# SEP00949BG.net
KiCad netlist of a schematic drawn in Altium Designer
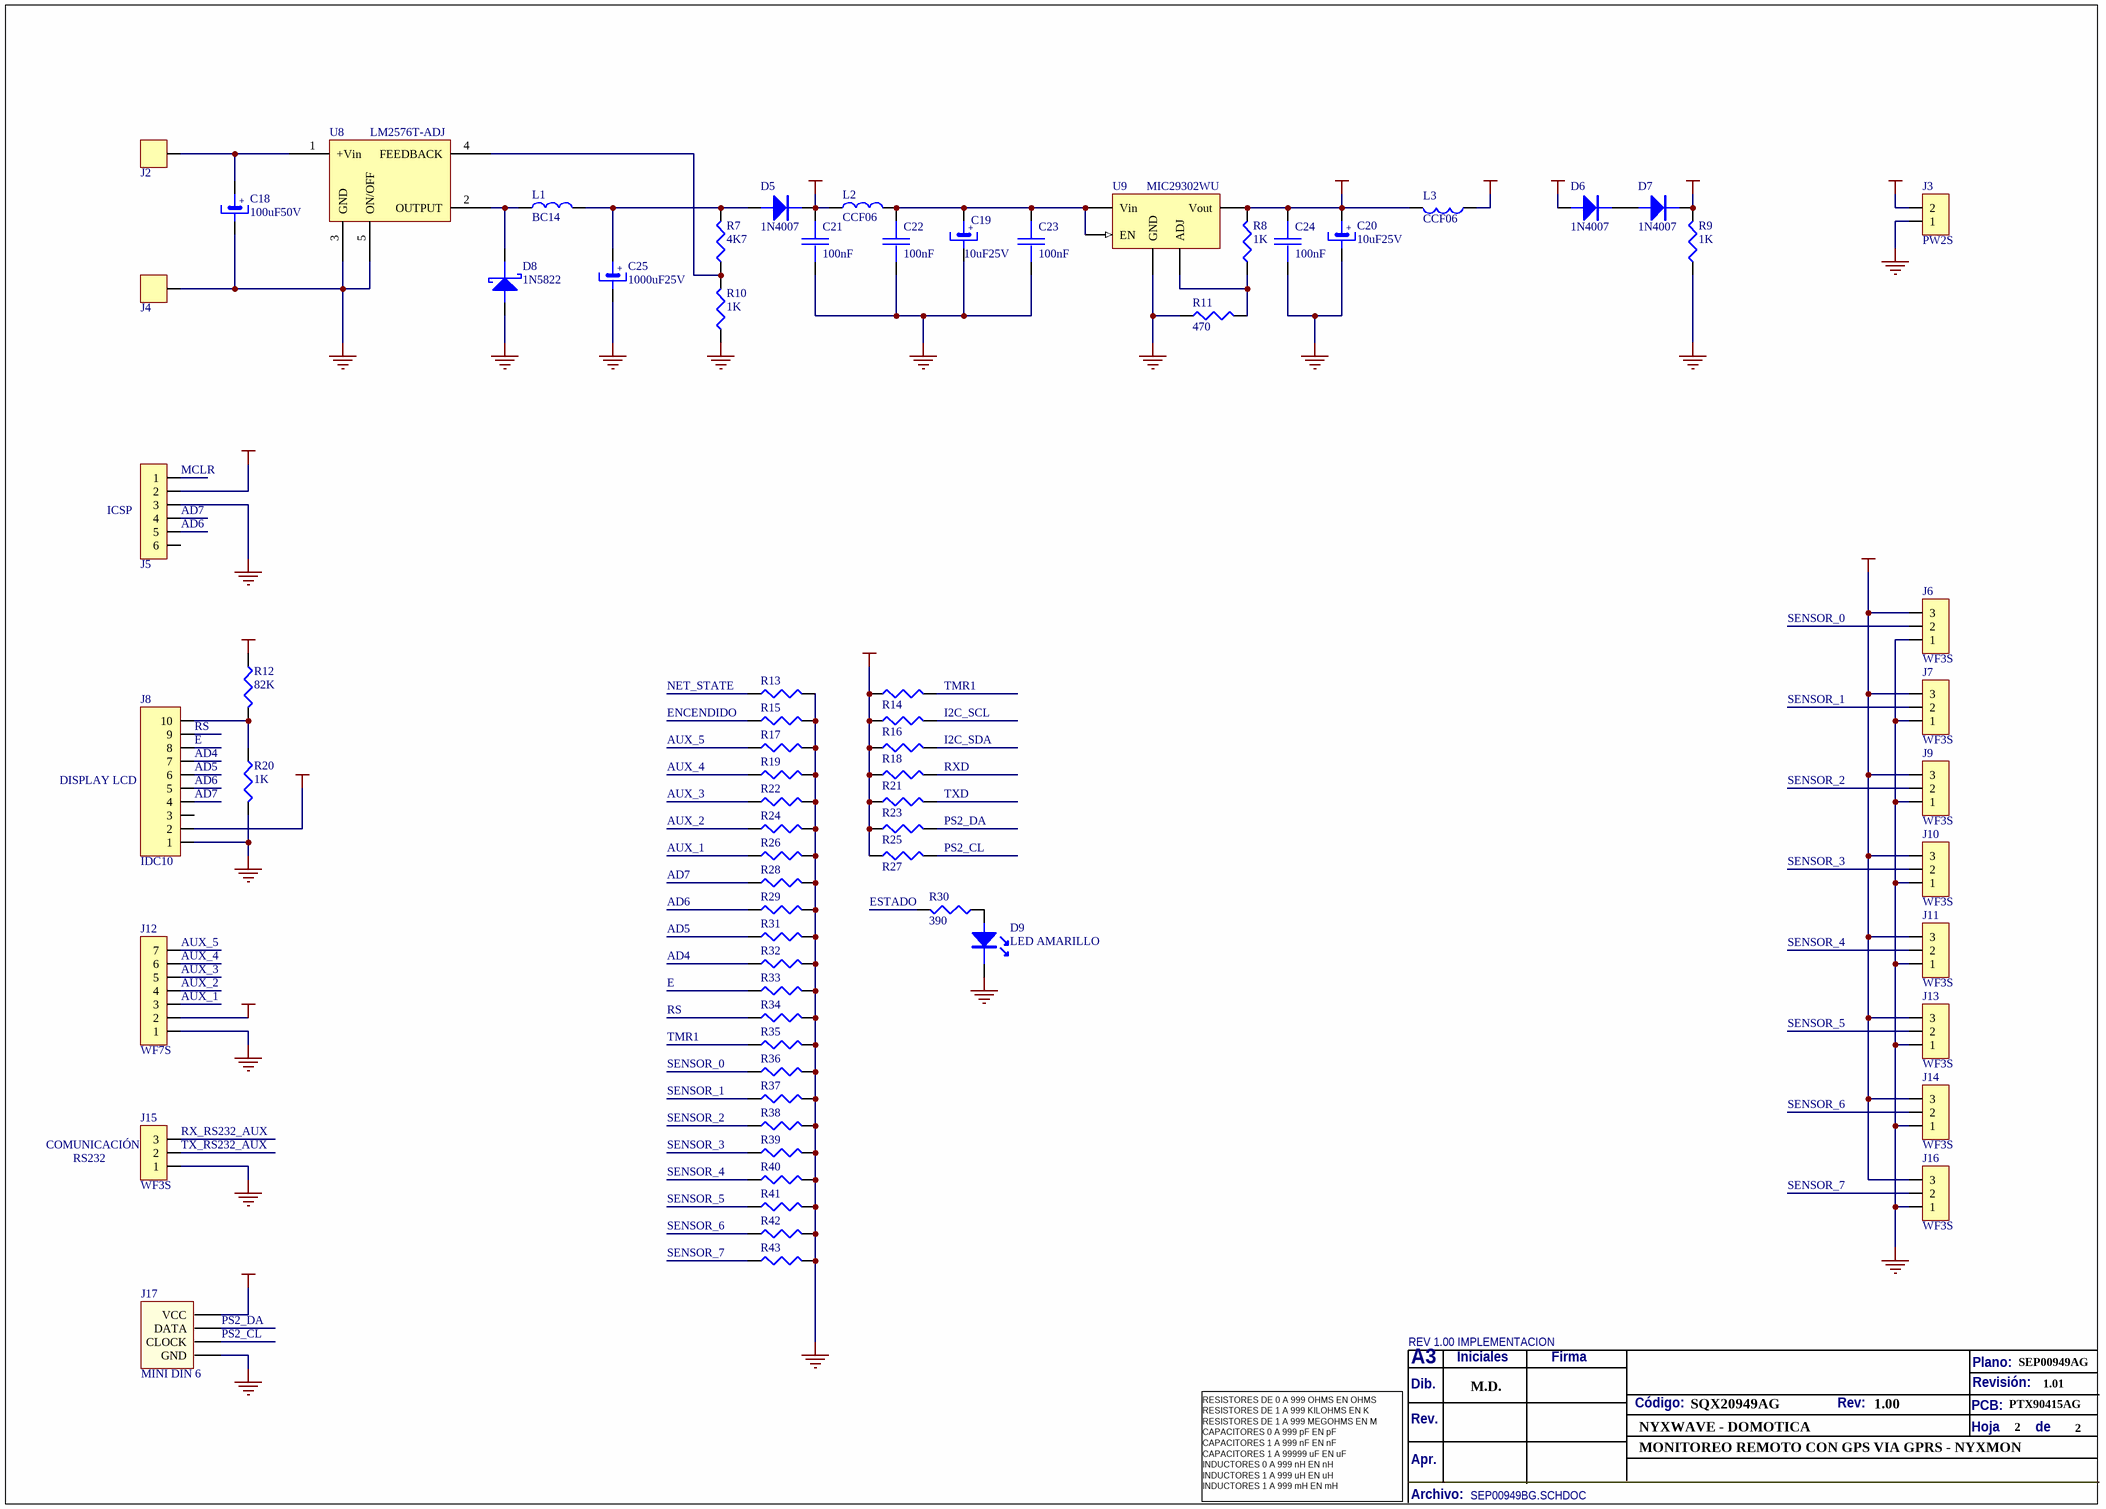
[diagram p0: SEP00949BG.SCHDOC]

(export (version "E")
  (design (tool "Eeschema 10.0.6"))
  (components
    (comp (ref "C18")
      (value "100uF50V")
      (footprint "CE 5.0/10.0")
      (description "CAPACITOR ELECTROLITICO RADIAL 10 X12 mm PASO 5 mm 50 V 100 uF")
      (libsource (lib "CAPACITORES ELECTROLITICOS") (part "100uF50V"))
    )
    (comp (ref "C19")
      (value "10uF25V")
      (footprint "CE 1.5/4.0")
      (description "CAPACITOR ELECTROLITICO RADIAL 5X7mm PASO 1.5mm 85ªC +/-20 25V 10uF")
      (libsource (lib "CAPACITORES ELECTROLITICOS") (part "10uF25V 4X7X1.5"))
    )
    (comp (ref "C20")
      (value "10uF25V")
      (footprint "CE 1.5/4.0")
      (description "CAPACITOR ELECTROLITICO RADIAL 5X7mm PASO 1.5mm 85ªC +/-20 25V 10uF")
      (libsource (lib "CAPACITORES ELECTROLITICOS") (part "10uF25V 4X7X1.5"))
    )
    (comp (ref "C21")
      (value "100nF")
      (footprint "0805")
      (description "CAPACITOR SMD 0805 X7R  50 V 100 nF")
      (libsource (lib "CAPACITORES SMD0805") (part "100n"))
    )
    (comp (ref "C22")
      (value "100nF")
      (footprint "0805")
      (description "CAPACITOR SMD 0805 X7R  50 V 100 nF")
      (libsource (lib "CAPACITORES SMD0805") (part "100n"))
    )
    (comp (ref "C23")
      (value "100nF")
      (footprint "0805")
      (description "CAPACITOR SMD 0805 X7R  50 V 100 nF")
      (libsource (lib "CAPACITORES SMD0805") (part "100n"))
    )
    (comp (ref "C24")
      (value "100nF")
      (footprint "0805")
      (description "CAPACITOR SMD 0805 X7R  50 V 100 nF")
      (libsource (lib "CAPACITORES SMD0805") (part "100n"))
    )
    (comp (ref "C25")
      (value "1000uF25V")
      (footprint "CE 5.0/10.0")
      (description "CAP ELECT RAD 1000UF 25V 10X20MM PASO 5MM 85ºC 20%")
      (libsource (lib "CAPACITORES ELECTROLITICOS") (part "1000uF25V"))
    )
    (comp (ref "D5")
      (value "1N4007")
      (footprint "DO-41_300")
      (description "1N4007 DO-41 DIODO")
      (libsource (lib "DIODOS") (part "1N4007 DO-41"))
    )
    (comp (ref "D6")
      (value "1N4007")
      (footprint "DO-41_300")
      (description "1N4007 DO-41 DIODO")
      (libsource (lib "DIODOS") (part "1N4007 DO-41"))
    )
    (comp (ref "D7")
      (value "1N4007")
      (footprint "DO-41_300")
      (description "1N4007 DO-41 DIODO")
      (libsource (lib "DIODOS") (part "1N4007 DO-41"))
    )
    (comp (ref "D8")
      (value "1N5822")
      (footprint "DO-201_300")
      (description "1N5822 DO-201 DIODO")
      (libsource (lib "DIODOS") (part "1N5822 DO-201"))
    )
    (comp (ref "D9")
      (value "LED AMARILLO")
      (footprint "LED 3MM")
      (description "LED AMARILLO 3MM")
      (libsource (lib "DIODOS") (part "LED AMARILLO 3MM"))
    )
    (comp (ref "J2")
      (value "WAGO236")
      (footprint "wago236")
      (description "WAGO 236-401 BORNE GRIS CLARO")
      (libsource (lib "CONECTORES") (part "WAGO 236"))
    )
    (comp (ref "J3")
      (value "PW2S")
      (footprint "PW2S")
      (description "PW2S HEADER .156\" RECTO 2 VIAS")
      (libsource (lib "CONECTORES") (part "PW2S"))
    )
    (comp (ref "J4")
      (value "WAGO236")
      (footprint "wago236")
      (description "WAGO 236-401 BORNE GRIS CLARO")
      (libsource (lib "CONECTORES") (part "WAGO 236"))
    )
    (comp (ref "J5")
      (value "HEADER6")
      (footprint "JUMPER_6A")
      (description "TIRA MOLEX 1X6 11MM MACHO RECTA PARA PCB")
      (libsource (lib "CONECTORES") (part "HEADER6"))
    )
    (comp (ref "J6")
      (value "WF3S")
      (footprint "WF3S")
      (description "WF3S HEADER .100\" RECTO 3 VIAS")
      (libsource (lib "CONECTORES") (part "WF3S"))
    )
    (comp (ref "J7")
      (value "WF3S")
      (footprint "WF3S")
      (description "WF3S HEADER .100\" RECTO 3 VIAS")
      (libsource (lib "CONECTORES") (part "WF3S"))
    )
    (comp (ref "J8")
      (value "IDC10")
      (footprint "IDC10")
      (description "CONECTOR IDC HEMBRA PCB NO POLARIZADO PASO 2.54 mm RECTO 2X5 VIAS")
      (libsource (lib "CONECTORES") (part "IDC10"))
    )
    (comp (ref "J9")
      (value "WF3S")
      (footprint "WF3S")
      (description "WF3S HEADER .100\" RECTO 3 VIAS")
      (libsource (lib "CONECTORES") (part "WF3S"))
    )
    (comp (ref "J10")
      (value "WF3S")
      (footprint "WF3S")
      (description "WF3S HEADER .100\" RECTO 3 VIAS")
      (libsource (lib "CONECTORES") (part "WF3S"))
    )
    (comp (ref "J11")
      (value "WF3S")
      (footprint "WF3S")
      (description "WF3S HEADER .100\" RECTO 3 VIAS")
      (libsource (lib "CONECTORES") (part "WF3S"))
    )
    (comp (ref "J12")
      (value "WF7S")
      (footprint "WF7S")
      (description "WF7S HEADER .100\" RECTO 7 VIAS")
      (libsource (lib "CONECTORES") (part "WF7S"))
    )
    (comp (ref "J13")
      (value "WF3S")
      (footprint "WF3S")
      (description "WF3S HEADER .100\" RECTO 3 VIAS")
      (libsource (lib "CONECTORES") (part "WF3S"))
    )
    (comp (ref "J14")
      (value "WF3S")
      (footprint "WF3S")
      (description "WF3S HEADER .100\" RECTO 3 VIAS")
      (libsource (lib "CONECTORES") (part "WF3S"))
    )
    (comp (ref "J15")
      (value "WF3S")
      (footprint "WF3S")
      (description "WF3S HEADER .100\" RECTO 3 VIAS")
      (libsource (lib "") (part "WF3S_1"))
    )
    (comp (ref "J16")
      (value "WF3S")
      (footprint "WF3S")
      (description "WF3S HEADER .100\" RECTO 3 VIAS")
      (libsource (lib "CONECTORES") (part "WF3S"))
    )
    (comp (ref "J17")
      (value "MINI DIN 6")
      (footprint "MINI DIN PCB")
      (description "CONECTOR MINI DIN 6 PARA PCB")
      (libsource (lib "mini din") (part "CONECTOR MINI DIN 6"))
    )
    (comp (ref "L1")
      (value "BC14")
      (footprint "BCC")
      (description "INDUCTOR BC14")
      (libsource (lib "INDUCTORES") (part "BC14"))
    )
    (comp (ref "L2")
      (value "CCF06")
      (footprint "AXIAL10X4_300")
      (description "INDUCTOR CCF06")
      (libsource (lib "INDUCTORES") (part "CCF06"))
    )
    (comp (ref "L3")
      (value "CCF06")
      (footprint "AXIAL10X4_300")
      (description "INDUCTOR CCF06")
      (libsource (lib "INDUCTORES") (part "CCF06"))
    )
    (comp (ref "R7")
      (value "4K7")
      (footprint "RES_MF1/2W_200")
      (description "RESISTOR METAL FILM 0.5 W 5% 4.7 KILOHMS")
      (libsource (lib "RESISTORES METAL FILM MEDIO WATT") (part "4K7"))
    )
    (comp (ref "R8")
      (value "1K")
      (footprint "RES_MF1/2W_200")
      (description "RESISTOR METAL FILM 0.5 W 5% 1 K OHMS")
      (libsource (lib "RESISTORES METAL FILM MEDIO WATT") (part "1K"))
    )
    (comp (ref "R9")
      (value "1K")
      (footprint "RES_MF1/2W_200")
      (description "RESISTOR METAL FILM 0.5 W 5% 1 K OHMS")
      (libsource (lib "RESISTORES METAL FILM MEDIO WATT") (part "1K"))
    )
    (comp (ref "R10")
      (value "1K")
      (footprint "RES_MF1/2W_200")
      (description "RESISTOR METAL FILM 0.5 W 5% 1 K OHMS")
      (libsource (lib "RESISTORES METAL FILM MEDIO WATT") (part "1K"))
    )
    (comp (ref "R11")
      (value "470")
      (footprint "RES_MF1/2W_200")
      (description "RESISTOR METAL FILM 0.5 W 5% 470 OHMS")
      (libsource (lib "RESISTORES METAL FILM MEDIO WATT") (part "470"))
    )
    (comp (ref "R12")
      (value "82K")
      (footprint "RES_MF1/2W_200")
      (description "RESISTOR METAL FILM 0.5 W 5% 82 KILOHMS")
      (libsource (lib "RESISTORES METAL FILM MEDIO WATT") (part "82K"))
    )
    (comp (ref "R13")
      (value "5K6")
      (footprint "0805")
      (description "RESISTOR SMD0805 0.125 W 5%  5.6 K OHMS")
      (libsource (lib "RESISTORES SMD0805") (part "5K6"))
    )
    (comp (ref "R14")
      (value "5K6")
      (footprint "0805")
      (description "RESISTOR SMD0805 0.125 W 5%  5.6 K OHMS")
      (libsource (lib "RESISTORES SMD0805") (part "5K6"))
    )
    (comp (ref "R15")
      (value "5K6")
      (footprint "0805")
      (description "RESISTOR SMD0805 0.125 W 5%  5.6 K OHMS")
      (libsource (lib "RESISTORES SMD0805") (part "5K6"))
    )
    (comp (ref "R16")
      (value "10K")
      (footprint "0805")
      (description "RESISTOR SMD0805 0.125 W 5%  10 K OHMS")
      (libsource (lib "RESISTORES SMD0805") (part "10K"))
    )
    (comp (ref "R17")
      (value "5K6")
      (footprint "0805")
      (description "RESISTOR SMD0805 0.125 W 5%  5.6 K OHMS")
      (libsource (lib "RESISTORES SMD0805") (part "5K6"))
    )
    (comp (ref "R18")
      (value "10K")
      (footprint "0805")
      (description "RESISTOR SMD0805 0.125 W 5%  10 K OHMS")
      (libsource (lib "RESISTORES SMD0805") (part "10K"))
    )
    (comp (ref "R19")
      (value "5K6")
      (footprint "0805")
      (description "RESISTOR SMD0805 0.125 W 5%  5.6 K OHMS")
      (libsource (lib "RESISTORES SMD0805") (part "5K6"))
    )
    (comp (ref "R20")
      (value "1K")
      (footprint "RES_MF1/2W_200")
      (description "RESISTOR METAL FILM 0.5 W 5% 1 K OHMS")
      (libsource (lib "RESISTORES METAL FILM MEDIO WATT") (part "1K"))
    )
    (comp (ref "R21")
      (value "100K")
      (footprint "0805")
      (description "RESISTOR SMD0805 0.125 W 5%  100 K OHMS")
      (libsource (lib "RESISTORES SMD0805") (part "100K"))
    )
    (comp (ref "R22")
      (value "5K6")
      (footprint "0805")
      (description "RESISTOR SMD0805 0.125 W 5%  5.6 K OHMS")
      (libsource (lib "RESISTORES SMD0805") (part "5K6"))
    )
    (comp (ref "R23")
      (value "100K")
      (footprint "0805")
      (description "RESISTOR SMD0805 0.125 W 5%  100 K OHMS")
      (libsource (lib "RESISTORES SMD0805") (part "100K"))
    )
    (comp (ref "R24")
      (value "5K6")
      (footprint "0805")
      (description "RESISTOR SMD0805 0.125 W 5%  5.6 K OHMS")
      (libsource (lib "RESISTORES SMD0805") (part "5K6"))
    )
    (comp (ref "R25")
      (value "5K6")
      (footprint "0805")
      (description "RESISTOR SMD0805 0.125 W 5%  5.6 K OHMS")
      (libsource (lib "RESISTORES SMD0805") (part "5K6"))
    )
    (comp (ref "R26")
      (value "5K6")
      (footprint "0805")
      (description "RESISTOR SMD0805 0.125 W 5%  5.6 K OHMS")
      (libsource (lib "RESISTORES SMD0805") (part "5K6"))
    )
    (comp (ref "R27")
      (value "5K6")
      (footprint "0805")
      (description "RESISTOR SMD0805 0.125 W 5%  5.6 K OHMS")
      (libsource (lib "RESISTORES SMD0805") (part "5K6"))
    )
    (comp (ref "R28")
      (value "5K6")
      (footprint "0805")
      (description "RESISTOR SMD0805 0.125 W 5%  5.6 K OHMS")
      (libsource (lib "RESISTORES SMD0805") (part "5K6"))
    )
    (comp (ref "R29")
      (value "5K6")
      (footprint "0805")
      (description "RESISTOR SMD0805 0.125 W 5%  5.6 K OHMS")
      (libsource (lib "RESISTORES SMD0805") (part "5K6"))
    )
    (comp (ref "R30")
      (value "390")
      (footprint "RES_MF1/2W_200")
      (description "RESISTOR METAL FILM 0.5 W 5% 390 OHMS")
      (libsource (lib "RESISTORES METAL FILM MEDIO WATT") (part "390"))
    )
    (comp (ref "R31")
      (value "5K6")
      (footprint "0805")
      (description "RESISTOR SMD0805 0.125 W 5%  5.6 K OHMS")
      (libsource (lib "RESISTORES SMD0805") (part "5K6"))
    )
    (comp (ref "R32")
      (value "5K6")
      (footprint "0805")
      (description "RESISTOR SMD0805 0.125 W 5%  5.6 K OHMS")
      (libsource (lib "RESISTORES SMD0805") (part "5K6"))
    )
    (comp (ref "R33")
      (value "5K6")
      (footprint "0805")
      (description "RESISTOR SMD0805 0.125 W 5%  5.6 K OHMS")
      (libsource (lib "RESISTORES SMD0805") (part "5K6"))
    )
    (comp (ref "R34")
      (value "5K6")
      (footprint "0805")
      (description "RESISTOR SMD0805 0.125 W 5%  5.6 K OHMS")
      (libsource (lib "RESISTORES SMD0805") (part "5K6"))
    )
    (comp (ref "R35")
      (value "5K6")
      (footprint "0805")
      (description "RESISTOR SMD0805 0.125 W 5%  5.6 K OHMS")
      (libsource (lib "RESISTORES SMD0805") (part "5K6"))
    )
    (comp (ref "R36")
      (value "150K")
      (footprint "0805")
      (description "RESISTOR SMD0805 0.125 W 5%  150 K OHMS")
      (libsource (lib "RESISTORES SMD0805") (part "150K"))
    )
    (comp (ref "R37")
      (value "150K")
      (footprint "0805")
      (description "RESISTOR SMD0805 0.125 W 5%  150 K OHMS")
      (libsource (lib "RESISTORES SMD0805") (part "150K"))
    )
    (comp (ref "R38")
      (value "150K")
      (footprint "0805")
      (description "RESISTOR SMD0805 0.125 W 5%  150 K OHMS")
      (libsource (lib "RESISTORES SMD0805") (part "150K"))
    )
    (comp (ref "R39")
      (value "150K")
      (footprint "0805")
      (description "RESISTOR SMD0805 0.125 W 5%  150 K OHMS")
      (libsource (lib "RESISTORES SMD0805") (part "150K"))
    )
    (comp (ref "R40")
      (value "150K")
      (footprint "0805")
      (description "RESISTOR SMD0805 0.125 W 5%  150 K OHMS")
      (libsource (lib "RESISTORES SMD0805") (part "150K"))
    )
    (comp (ref "R41")
      (value "150K")
      (footprint "0805")
      (description "RESISTOR SMD0805 0.125 W 5%  150 K OHMS")
      (libsource (lib "RESISTORES SMD0805") (part "150K"))
    )
    (comp (ref "R42")
      (value "150K")
      (footprint "0805")
      (description "RESISTOR SMD0805 0.125 W 5%  150 K OHMS")
      (libsource (lib "RESISTORES SMD0805") (part "150K"))
    )
    (comp (ref "R43")
      (value "150K")
      (footprint "0805")
      (description "RESISTOR SMD0805 0.125 W 5%  150 K OHMS")
      (libsource (lib "RESISTORES SMD0805") (part "150K"))
    )
    (comp (ref "U8")
      (value "LM2576T-ADJ")
      (footprint "TO-220-5V")
      (description "LM2576T-ADJ TO-220-5 CIRC INT")
      (libsource (lib "CIRCUITOS INTEGRADOS DIP") (part "LM2576T-ADJ"))
    )
    (comp (ref "U9")
      (value "MIC29302WU")
      (footprint "TO-220-5S")
      (description "MIC29302WU TO-220 (T) HIGH CURRENT LOW DROPOUT REGULATORS")
      (libsource (lib "CIRCUITOS INTEGRADOS DIP") (part "MIC29302WU"))
    )
  )
  (nets
    (net (code "1") (name "+5V") (class "Default")
      (node (ref "C20") (pin "1") (pinfunction "1_1") (pintype "passive"))
      (node (ref "C24") (pin "2") (pintype "passive"))
      (node (ref "D6") (pin "A") (pinfunction "A_A") (pintype "passive"))
      (node (ref "J10") (pin "3") (pinfunction "3_3") (pintype "passive"))
      (node (ref "J11") (pin "3") (pinfunction "3_3") (pintype "passive"))
      (node (ref "J12") (pin "2") (pinfunction "2_2") (pintype "passive"))
      (node (ref "J13") (pin "3") (pinfunction "3_3") (pintype "passive"))
      (node (ref "J14") (pin "3") (pinfunction "3_3") (pintype "passive"))
      (node (ref "J16") (pin "3") (pinfunction "3_3") (pintype "passive"))
      (node (ref "J17") (pin "4") (pinfunction "VCC_4") (pintype "power_in"))
      (node (ref "J6") (pin "3") (pinfunction "3_3") (pintype "passive"))
      (node (ref "J7") (pin "3") (pinfunction "3_3") (pintype "passive"))
      (node (ref "J8") (pin "2") (pinfunction "2_2") (pintype "passive"))
      (node (ref "J9") (pin "3") (pinfunction "3_3") (pintype "passive"))
      (node (ref "L3") (pin "2") (pintype "passive"))
      (node (ref "R12") (pin "2") (pintype "passive"))
      (node (ref "R14") (pin "2") (pintype "passive"))
      (node (ref "R16") (pin "2") (pintype "passive"))
      (node (ref "R18") (pin "2") (pintype "passive"))
      (node (ref "R21") (pin "2") (pintype "passive"))
      (node (ref "R23") (pin "2") (pintype "passive"))
      (node (ref "R25") (pin "2") (pintype "passive"))
      (node (ref "R27") (pin "2") (pintype "passive"))
      (node (ref "R8") (pin "2") (pintype "passive"))
      (node (ref "U9") (pin "4") (pinfunction "Vout_4") (pintype "passive"))
    )
    (net (code "2") (name "+7V") (class "Default")
      (node (ref "C21") (pin "2") (pintype "passive"))
      (node (ref "D5") (pin "K") (pinfunction "K_K") (pintype "passive"))
      (node (ref "J3") (pin "2") (pinfunction "2_2") (pintype "passive"))
      (node (ref "L2") (pin "1") (pintype "passive"))
    )
    (net (code "6") (name "/AD4") (class "Default")
      (node (ref "J8") (pin "7") (pinfunction "7_7") (pintype "passive"))
      (node (ref "R32") (pin "1") (pintype "passive"))
    )
    (net (code "7") (name "/AD5") (class "Default")
      (node (ref "J8") (pin "6") (pinfunction "6_6") (pintype "passive"))
      (node (ref "R31") (pin "1") (pintype "passive"))
    )
    (net (code "8") (name "/AD6") (class "Default")
      (node (ref "J5") (pin "5") (pinfunction "5_5") (pintype "passive"))
      (node (ref "J8") (pin "5") (pinfunction "5_5") (pintype "passive"))
      (node (ref "R29") (pin "1") (pintype "passive"))
    )
    (net (code "9") (name "/AD7") (class "Default")
      (node (ref "J5") (pin "4") (pinfunction "4_4") (pintype "passive"))
      (node (ref "J8") (pin "4") (pinfunction "4_4") (pintype "passive"))
      (node (ref "R28") (pin "1") (pintype "passive"))
    )
    (net (code "10") (name "/AUX_1") (class "Default")
      (node (ref "J12") (pin "3") (pinfunction "3_3") (pintype "passive"))
      (node (ref "R26") (pin "1") (pintype "passive"))
    )
    (net (code "11") (name "/AUX_2") (class "Default")
      (node (ref "J12") (pin "4") (pinfunction "4_4") (pintype "passive"))
      (node (ref "R24") (pin "1") (pintype "passive"))
    )
    (net (code "12") (name "/AUX_3") (class "Default")
      (node (ref "J12") (pin "5") (pinfunction "5_5") (pintype "passive"))
      (node (ref "R22") (pin "1") (pintype "passive"))
    )
    (net (code "13") (name "/AUX_4") (class "Default")
      (node (ref "J12") (pin "6") (pinfunction "6_6") (pintype "passive"))
      (node (ref "R19") (pin "1") (pintype "passive"))
    )
    (net (code "14") (name "/AUX_5") (class "Default")
      (node (ref "J12") (pin "7") (pinfunction "7_7") (pintype "passive"))
      (node (ref "R17") (pin "1") (pintype "passive"))
    )
    (net (code "15") (name "/E") (class "Default")
      (node (ref "J8") (pin "8") (pinfunction "8_8") (pintype "passive"))
      (node (ref "R33") (pin "1") (pintype "passive"))
    )
    (net (code "16") (name "/ENCENDIDO") (class "Default") (node (ref "R15") (pin "1") (pintype "passive")))
    (net (code "17") (name "/ESTADO") (class "Default") (node (ref "R30") (pin "2") (pintype "passive")))
    (net (code "18") (name "/I2C_SCL") (class "Default") (node (ref "R16") (pin "1") (pintype "passive")))
    (net (code "19") (name "/I2C_SDA") (class "Default") (node (ref "R18") (pin "1") (pintype "passive")))
    (net (code "21") (name "/MCLR") (class "Default")
      (node (ref "J5") (pin "1") (pinfunction "1_1") (pintype "passive"))
    )
    (net (code "23") (name "/NET_STATE") (class "Default") (node (ref "R13") (pin "1") (pintype "passive")))
    (net (code "25") (name "/PS2_CL") (class "Default")
      (node (ref "J17") (pin "5") (pinfunction "CLOCK_5") (pintype "passive"))
      (node (ref "R27") (pin "1") (pintype "passive"))
    )
    (net (code "26") (name "/PS2_DA") (class "Default")
      (node (ref "J17") (pin "1") (pinfunction "DATA_1") (pintype "passive"))
      (node (ref "R25") (pin "1") (pintype "passive"))
    )
    (net (code "28") (name "/RS") (class "Default")
      (node (ref "J8") (pin "9") (pinfunction "9_9") (pintype "passive"))
      (node (ref "R34") (pin "1") (pintype "passive"))
    )
    (net (code "29") (name "/RXD") (class "Default") (node (ref "R21") (pin "1") (pintype "passive")))
    (net (code "30") (name "/RX_RS232_AUX") (class "Default")
      (node (ref "J15") (pin "3") (pinfunction "3_3") (pintype "passive"))
    )
    (net (code "31") (name "/SENSOR_0") (class "Default")
      (node (ref "J6") (pin "2") (pinfunction "2_2") (pintype "passive"))
      (node (ref "R36") (pin "1") (pintype "passive"))
    )
    (net (code "32") (name "/SENSOR_1") (class "Default")
      (node (ref "J7") (pin "2") (pinfunction "2_2") (pintype "passive"))
      (node (ref "R37") (pin "1") (pintype "passive"))
    )
    (net (code "33") (name "/SENSOR_2") (class "Default")
      (node (ref "J9") (pin "2") (pinfunction "2_2") (pintype "passive"))
      (node (ref "R38") (pin "1") (pintype "passive"))
    )
    (net (code "34") (name "/SENSOR_3") (class "Default")
      (node (ref "J10") (pin "2") (pinfunction "2_2") (pintype "passive"))
      (node (ref "R39") (pin "1") (pintype "passive"))
    )
    (net (code "35") (name "/SENSOR_4") (class "Default")
      (node (ref "J11") (pin "2") (pinfunction "2_2") (pintype "passive"))
      (node (ref "R40") (pin "1") (pintype "passive"))
    )
    (net (code "36") (name "/SENSOR_5") (class "Default")
      (node (ref "J13") (pin "2") (pinfunction "2_2") (pintype "passive"))
      (node (ref "R41") (pin "1") (pintype "passive"))
    )
    (net (code "37") (name "/SENSOR_6") (class "Default")
      (node (ref "J14") (pin "2") (pinfunction "2_2") (pintype "passive"))
      (node (ref "R42") (pin "1") (pintype "passive"))
    )
    (net (code "38") (name "/SENSOR_7") (class "Default")
      (node (ref "J16") (pin "2") (pinfunction "2_2") (pintype "passive"))
      (node (ref "R43") (pin "1") (pintype "passive"))
    )
    (net (code "41") (name "/TMR1") (class "Default")
      (node (ref "R14") (pin "1") (pintype "passive"))
      (node (ref "R35") (pin "1") (pintype "passive"))
    )
    (net (code "42") (name "/TXD") (class "Default") (node (ref "R23") (pin "1") (pintype "passive")))
    (net (code "43") (name "/TX_RS232_AUX") (class "Default")
      (node (ref "J15") (pin "2") (pinfunction "2_2") (pintype "passive"))
    )
    (net (code "44") (name "GND") (class "Default")
      (node (ref "C18") (pin "2") (pinfunction "2_2") (pintype "passive"))
      (node (ref "C19") (pin "2") (pinfunction "2_2") (pintype "passive"))
      (node (ref "C20") (pin "2") (pinfunction "2_2") (pintype "passive"))
      (node (ref "C21") (pin "1") (pintype "passive"))
      (node (ref "C22") (pin "1") (pintype "passive"))
      (node (ref "C23") (pin "1") (pintype "passive"))
      (node (ref "C24") (pin "1") (pintype "passive"))
      (node (ref "C25") (pin "2") (pinfunction "2_2") (pintype "passive"))
      (node (ref "D8") (pin "A") (pinfunction "A_A") (pintype "passive"))
      (node (ref "D9") (pin "K") (pinfunction "K_K") (pintype "passive"))
      (node (ref "J10") (pin "1") (pinfunction "1_1") (pintype "passive"))
      (node (ref "J11") (pin "1") (pinfunction "1_1") (pintype "passive"))
      (node (ref "J12") (pin "1") (pinfunction "1_1") (pintype "passive"))
      (node (ref "J13") (pin "1") (pinfunction "1_1") (pintype "passive"))
      (node (ref "J14") (pin "1") (pinfunction "1_1") (pintype "passive"))
      (node (ref "J15") (pin "1") (pinfunction "1_1") (pintype "passive"))
      (node (ref "J16") (pin "1") (pinfunction "1_1") (pintype "passive"))
      (node (ref "J17") (pin "3") (pinfunction "GND_3") (pintype "passive"))
      (node (ref "J3") (pin "1") (pinfunction "1_1") (pintype "passive"))
      (node (ref "J4") (pin "1") (pinfunction "1_1") (pintype "passive"))
      (node (ref "J5") (pin "3") (pinfunction "3_3") (pintype "passive"))
      (node (ref "J6") (pin "1") (pinfunction "1_1") (pintype "passive"))
      (node (ref "J7") (pin "1") (pinfunction "1_1") (pintype "passive"))
      (node (ref "J8") (pin "1") (pinfunction "1_1") (pintype "passive"))
      (node (ref "J9") (pin "1") (pinfunction "1_1") (pintype "passive"))
      (node (ref "R10") (pin "1") (pintype "passive"))
      (node (ref "R11") (pin "1") (pintype "passive"))
      (node (ref "R13") (pin "2") (pintype "passive"))
      (node (ref "R15") (pin "2") (pintype "passive"))
      (node (ref "R17") (pin "2") (pintype "passive"))
      (node (ref "R19") (pin "2") (pintype "passive"))
      (node (ref "R20") (pin "1") (pintype "passive"))
      (node (ref "R22") (pin "2") (pintype "passive"))
      (node (ref "R24") (pin "2") (pintype "passive"))
      (node (ref "R26") (pin "2") (pintype "passive"))
      (node (ref "R28") (pin "2") (pintype "passive"))
      (node (ref "R29") (pin "2") (pintype "passive"))
      (node (ref "R31") (pin "2") (pintype "passive"))
      (node (ref "R32") (pin "2") (pintype "passive"))
      (node (ref "R33") (pin "2") (pintype "passive"))
      (node (ref "R34") (pin "2") (pintype "passive"))
      (node (ref "R35") (pin "2") (pintype "passive"))
      (node (ref "R36") (pin "2") (pintype "passive"))
      (node (ref "R37") (pin "2") (pintype "passive"))
      (node (ref "R38") (pin "2") (pintype "passive"))
      (node (ref "R39") (pin "2") (pintype "passive"))
      (node (ref "R40") (pin "2") (pintype "passive"))
      (node (ref "R41") (pin "2") (pintype "passive"))
      (node (ref "R42") (pin "2") (pintype "passive"))
      (node (ref "R43") (pin "2") (pintype "passive"))
      (node (ref "R9") (pin "1") (pintype "passive"))
      (node (ref "U8") (pin "3") (pinfunction "GND_3") (pintype "passive"))
      (node (ref "U8") (pin "5") (pinfunction "ON/OFF_5") (pintype "passive"))
      (node (ref "U9") (pin "3") (pinfunction "GND_3") (pintype "passive"))
    )
    (net (code "45") (name "Net-(C25-Pad1)") (class "Default")
      (node (ref "C25") (pin "1") (pinfunction "1_1") (pintype "passive"))
      (node (ref "D5") (pin "A") (pinfunction "A_A") (pintype "passive"))
      (node (ref "L1") (pin "2") (pintype "passive"))
      (node (ref "R7") (pin "2") (pintype "passive"))
    )
    (net (code "46") (name "Net-(D6-PadK)") (class "Default")
      (node (ref "D6") (pin "K") (pinfunction "K_K") (pintype "passive"))
      (node (ref "D7") (pin "A") (pinfunction "A_A") (pintype "passive"))
    )
    (net (code "47") (name "Net-(D9-PadA)") (class "Default")
      (node (ref "D9") (pin "A") (pinfunction "A_A") (pintype "passive"))
      (node (ref "R30") (pin "1") (pintype "passive"))
    )
    (net (code "48") (name "Net-(J8-Pad10)") (class "Default")
      (node (ref "J8") (pin "10") (pinfunction "10_10") (pintype "passive"))
      (node (ref "R12") (pin "1") (pintype "passive"))
      (node (ref "R20") (pin "2") (pintype "passive"))
    )
    (net (code "49") (name "Net-(U8-+Vin)") (class "Default")
      (node (ref "C18") (pin "1") (pinfunction "1_1") (pintype "passive"))
      (node (ref "J2") (pin "1") (pinfunction "1_1") (pintype "passive"))
      (node (ref "U8") (pin "1") (pinfunction "+Vin_1") (pintype "passive"))
    )
    (net (code "50") (name "Net-(U8-FEEDBACK)") (class "Default")
      (node (ref "R10") (pin "2") (pintype "passive"))
      (node (ref "R7") (pin "1") (pintype "passive"))
      (node (ref "U8") (pin "4") (pinfunction "FEEDBACK_4") (pintype "passive"))
    )
    (net (code "51") (name "Net-(U8-OUTPUT)") (class "Default")
      (node (ref "D8") (pin "K") (pinfunction "K_K") (pintype "passive"))
      (node (ref "L1") (pin "1") (pintype "passive"))
      (node (ref "U8") (pin "2") (pinfunction "OUTPUT_2") (pintype "passive"))
    )
    (net (code "52") (name "Net-(U9-ADJ)") (class "Default")
      (node (ref "R11") (pin "2") (pintype "passive"))
      (node (ref "R8") (pin "1") (pintype "passive"))
      (node (ref "U9") (pin "5") (pinfunction "ADJ_5") (pintype "passive"))
    )
    (net (code "53") (name "Net-(U9-EN)") (class "Default")
      (node (ref "C19") (pin "1") (pinfunction "1_1") (pintype "passive"))
      (node (ref "C22") (pin "2") (pintype "passive"))
      (node (ref "C23") (pin "2") (pintype "passive"))
      (node (ref "L2") (pin "2") (pintype "passive"))
      (node (ref "U9") (pin "1") (pinfunction "EN_1") (pintype "input"))
      (node (ref "U9") (pin "2") (pinfunction "Vin_2") (pintype "power_in"))
    )
    (net (code "54") (name "VBAT") (class "Default")
      (node (ref "D7") (pin "K") (pinfunction "K_K") (pintype "passive"))
      (node (ref "R9") (pin "2") (pintype "passive"))
    )
    (net (code "55") (name "VDD") (class "Default")
      (node (ref "J5") (pin "2") (pinfunction "2_2") (pintype "passive"))
      (node (ref "L3") (pin "1") (pintype "passive"))
    )
    (net (code "56") (name "unconnected-(J5-Pad6)") (class "Default")
      (node (ref "J5") (pin "6") (pinfunction "6_6") (pintype "passive"))
    )
    (net (code "57") (name "unconnected-(J8-Pad3)") (class "Default")
      (node (ref "J8") (pin "3") (pinfunction "3_3") (pintype "passive"))
    )
  )
)
